# mcuboard.net
KiCad netlist of a schematic drawn in EAGLE
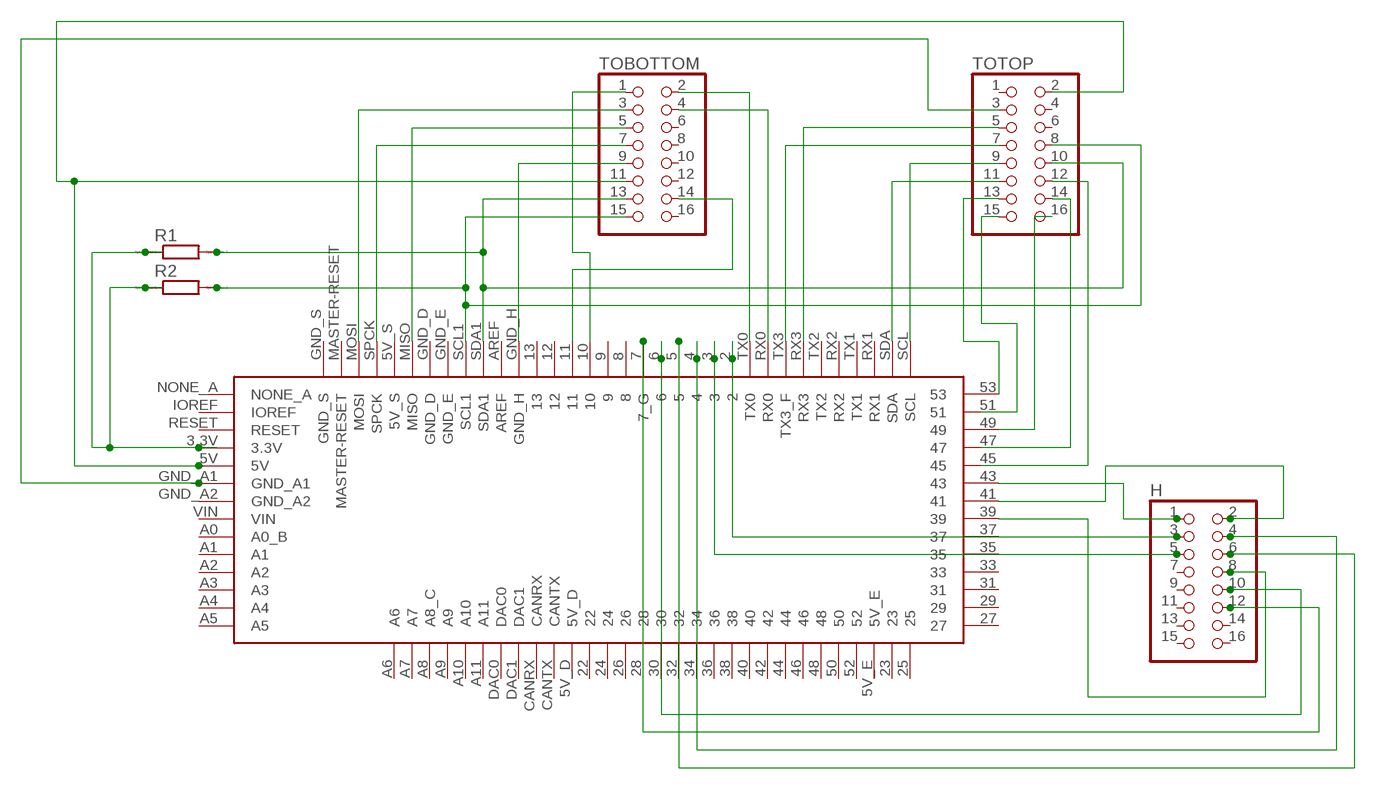
[diagram p0: schematic, sheet 1]

(export (version "E")
  (design (tool "Eeschema 10.0.6"))
  (components
    (comp (ref "H")
      (value "PINHD-2X8")
      (footprint "eagle-import:2X08")
      (libsource (lib "eagle-import") (part "PINHD-2X8"))
    )
    (comp (ref "R1")
      (value "R-EU_0207_12")
      (footprint "eagle-import:0207_12")
      (libsource (lib "eagle-import") (part "R-EU_0207_12"))
    )
    (comp (ref "R2")
      (value "R-EU_0207_12")
      (footprint "eagle-import:0207_12")
      (libsource (lib "eagle-import") (part "R-EU_0207_12"))
    )
    (comp (ref "TOBOTTOM")
      (value "PINHD-2X8")
      (footprint "eagle-import:2X08")
      (libsource (lib "eagle-import") (part "PINHD-2X8"))
    )
    (comp (ref "TOTOP")
      (value "PINHD-2X8")
      (footprint "eagle-import:2X08")
      (libsource (lib "eagle-import") (part "PINHD-2X8"))
    )
    (comp (ref "U$1")
      (value "IDUINO1")
      (footprint "eagle-import:IDUINO_PAC")
      (libsource (lib "eagle-import") (part "IDUINO1"))
    )
  )
  (nets
    (net (code "1") (name "Net-(H-Pad1)") (class "Default")
      (node (ref "H") (pin "1") (pinfunction "1_1") (pintype "passive"))
      (node (ref "U$1") (pin "43") (pinfunction "43_43") (pintype "bidirectional"))
    )
    (net (code "2") (name "Net-(H-Pad2)") (class "Default")
      (node (ref "H") (pin "2") (pinfunction "2_2") (pintype "passive"))
      (node (ref "U$1") (pin "41") (pinfunction "41_41") (pintype "bidirectional"))
    )
    (net (code "3") (name "Net-(H-Pad3)") (class "Default")
      (node (ref "H") (pin "3") (pinfunction "3_3") (pintype "passive"))
      (node (ref "U$1") (pin "2") (pinfunction "2_2") (pintype "bidirectional"))
    )
    (net (code "4") (name "Net-(H-Pad4)") (class "Default")
      (node (ref "H") (pin "4") (pinfunction "4_4") (pintype "passive"))
      (node (ref "U$1") (pin "4") (pinfunction "4_4") (pintype "bidirectional"))
    )
    (net (code "5") (name "Net-(H-Pad5)") (class "Default")
      (node (ref "H") (pin "5") (pinfunction "5_5") (pintype "passive"))
      (node (ref "U$1") (pin "3") (pinfunction "3_3") (pintype "bidirectional"))
    )
    (net (code "6") (name "Net-(H-Pad6)") (class "Default")
      (node (ref "H") (pin "6") (pinfunction "6_6") (pintype "passive"))
      (node (ref "U$1") (pin "5") (pinfunction "5_5") (pintype "bidirectional"))
    )
    (net (code "7") (name "Net-(H-Pad8)") (class "Default")
      (node (ref "H") (pin "8") (pinfunction "8_8") (pintype "passive"))
      (node (ref "U$1") (pin "39") (pinfunction "39_39") (pintype "bidirectional"))
    )
    (net (code "8") (name "Net-(H-Pad10)") (class "Default")
      (node (ref "H") (pin "10") (pinfunction "10_10") (pintype "passive"))
      (node (ref "U$1") (pin "6") (pinfunction "6_6") (pintype "bidirectional"))
    )
    (net (code "9") (name "Net-(R1-Pad1)") (class "Default")
      (node (ref "R1") (pin "1") (pinfunction "1_1") (pintype "passive"))
      (node (ref "R2") (pin "1") (pinfunction "1_1") (pintype "passive"))
      (node (ref "U$1") (pin "3.3V") (pinfunction "3.3V_3.3V") (pintype "bidirectional"))
    )
    (net (code "10") (name "Net-(R1-Pad2)") (class "Default")
      (node (ref "R1") (pin "2") (pinfunction "2_2") (pintype "passive"))
      (node (ref "TOBOTTOM") (pin "13") (pinfunction "13_13") (pintype "passive"))
      (node (ref "TOTOP") (pin "10") (pinfunction "10_10") (pintype "passive"))
      (node (ref "U$1") (pin "SDA1") (pinfunction "SDA1_SDA1") (pintype "bidirectional"))
    )
    (net (code "11") (name "Net-(R2-Pad2)") (class "Default")
      (node (ref "R2") (pin "2") (pinfunction "2_2") (pintype "passive"))
      (node (ref "TOBOTTOM") (pin "15") (pinfunction "15_15") (pintype "passive"))
      (node (ref "TOTOP") (pin "8") (pinfunction "8_8") (pintype "passive"))
      (node (ref "U$1") (pin "SCL1") (pinfunction "SCL1_SCL1") (pintype "bidirectional"))
    )
    (net (code "12") (name "Net-(TOBOTTOM-Pad1)") (class "Default")
      (node (ref "TOBOTTOM") (pin "1") (pinfunction "1_1") (pintype "passive"))
      (node (ref "U$1") (pin "10") (pinfunction "10_10") (pintype "bidirectional"))
    )
    (net (code "13") (name "Net-(TOBOTTOM-Pad2)") (class "Default")
      (node (ref "TOBOTTOM") (pin "2") (pinfunction "2_2") (pintype "passive"))
      (node (ref "U$1") (pin "TX0") (pinfunction "TX0_TX0") (pintype "bidirectional"))
    )
    (net (code "14") (name "Net-(TOBOTTOM-Pad3)") (class "Default")
      (node (ref "TOBOTTOM") (pin "3") (pinfunction "3_3") (pintype "passive"))
      (node (ref "U$1") (pin "MOSI") (pinfunction "MOSI_MOSI") (pintype "bidirectional"))
    )
    (net (code "15") (name "Net-(TOBOTTOM-Pad4)") (class "Default")
      (node (ref "TOBOTTOM") (pin "4") (pinfunction "4_4") (pintype "passive"))
      (node (ref "U$1") (pin "RX0") (pinfunction "RX0_RX0") (pintype "bidirectional"))
    )
    (net (code "16") (name "Net-(TOBOTTOM-Pad5)") (class "Default")
      (node (ref "TOBOTTOM") (pin "5") (pinfunction "5_5") (pintype "passive"))
      (node (ref "U$1") (pin "MISO") (pinfunction "MISO_MISO") (pintype "bidirectional"))
    )
    (net (code "17") (name "Net-(TOBOTTOM-Pad7)") (class "Default")
      (node (ref "TOBOTTOM") (pin "7") (pinfunction "7_7") (pintype "passive"))
      (node (ref "U$1") (pin "SPCK") (pinfunction "SPCK_SPCK") (pintype "bidirectional"))
    )
    (net (code "18") (name "Net-(TOBOTTOM-Pad9)") (class "Default")
      (node (ref "TOBOTTOM") (pin "9") (pinfunction "9_9") (pintype "passive"))
      (node (ref "U$1") (pin "GND_H") (pinfunction "GND_H_GND_H") (pintype "bidirectional"))
    )
    (net (code "19") (name "Net-(TOBOTTOM-Pad11)") (class "Default")
      (node (ref "TOBOTTOM") (pin "11") (pinfunction "11_11") (pintype "passive"))
      (node (ref "TOTOP") (pin "2") (pinfunction "2_2") (pintype "passive"))
      (node (ref "U$1") (pin "5V") (pinfunction "5V_5V") (pintype "bidirectional"))
    )
    (net (code "20") (name "Net-(TOBOTTOM-Pad14)") (class "Default")
      (node (ref "TOBOTTOM") (pin "14") (pinfunction "14_14") (pintype "passive"))
      (node (ref "U$1") (pin "11") (pinfunction "11_11") (pintype "bidirectional"))
    )
    (net (code "21") (name "Net-(TOTOP-Pad3)") (class "Default")
      (node (ref "TOTOP") (pin "3") (pinfunction "3_3") (pintype "passive"))
      (node (ref "U$1") (pin "GND_A1") (pinfunction "GND_A1_GND_A1") (pintype "bidirectional"))
    )
    (net (code "22") (name "Net-(TOTOP-Pad5)") (class "Default")
      (node (ref "TOTOP") (pin "5") (pinfunction "5_5") (pintype "passive"))
      (node (ref "U$1") (pin "RX3") (pinfunction "RX3_RX3") (pintype "bidirectional"))
    )
    (net (code "23") (name "Net-(TOTOP-Pad9)") (class "Default")
      (node (ref "TOTOP") (pin "9") (pinfunction "9_9") (pintype "passive"))
      (node (ref "U$1") (pin "SCL") (pinfunction "SCL_SCL") (pintype "bidirectional"))
    )
    (net (code "24") (name "Net-(TOTOP-Pad11)") (class "Default")
      (node (ref "TOTOP") (pin "11") (pinfunction "11_11") (pintype "passive"))
      (node (ref "U$1") (pin "SDA") (pinfunction "SDA_SDA") (pintype "bidirectional"))
    )
    (net (code "25") (name "Net-(TOTOP-Pad13)") (class "Default")
      (node (ref "TOTOP") (pin "13") (pinfunction "13_13") (pintype "passive"))
      (node (ref "U$1") (pin "53") (pinfunction "53_53") (pintype "bidirectional"))
    )
    (net (code "26") (name "Net-(TOTOP-Pad16)") (class "Default")
      (node (ref "TOTOP") (pin "16") (pinfunction "16_16") (pintype "passive"))
      (node (ref "U$1") (pin "49") (pinfunction "49_49") (pintype "bidirectional"))
    )
    (net (code "27") (name "Net-(U$1-7_G)") (class "Default")
      (node (ref "H") (pin "12") (pinfunction "12_12") (pintype "passive"))
      (node (ref "U$1") (pin "7") (pinfunction "7_G_7") (pintype "bidirectional"))
    )
    (net (code "28") (name "Net-(U$1-TX3_F)") (class "Default")
      (node (ref "TOTOP") (pin "7") (pinfunction "7_7") (pintype "passive"))
      (node (ref "U$1") (pin "TX3") (pinfunction "TX3_F_TX3") (pintype "bidirectional"))
    )
    (net (code "29") (name "unconnected-(H-Pad7)") (class "Default")
      (node (ref "H") (pin "7") (pinfunction "7_7") (pintype "passive"))
    )
    (net (code "30") (name "unconnected-(H-Pad9)") (class "Default")
      (node (ref "H") (pin "9") (pinfunction "9_9") (pintype "passive"))
    )
    (net (code "31") (name "unconnected-(H-Pad11)") (class "Default")
      (node (ref "H") (pin "11") (pinfunction "11_11") (pintype "passive"))
    )
    (net (code "32") (name "unconnected-(H-Pad13)") (class "Default")
      (node (ref "H") (pin "13") (pinfunction "13_13") (pintype "passive"))
    )
    (net (code "33") (name "unconnected-(H-Pad14)") (class "Default")
      (node (ref "H") (pin "14") (pinfunction "14_14") (pintype "passive"))
    )
    (net (code "34") (name "unconnected-(H-Pad15)") (class "Default")
      (node (ref "H") (pin "15") (pinfunction "15_15") (pintype "passive"))
    )
    (net (code "35") (name "unconnected-(H-Pad16)") (class "Default")
      (node (ref "H") (pin "16") (pinfunction "16_16") (pintype "passive"))
    )
    (net (code "36") (name "unconnected-(TOBOTTOM-Pad6)") (class "Default")
      (node (ref "TOBOTTOM") (pin "6") (pinfunction "6_6") (pintype "passive"))
    )
    (net (code "37") (name "unconnected-(TOBOTTOM-Pad8)") (class "Default")
      (node (ref "TOBOTTOM") (pin "8") (pinfunction "8_8") (pintype "passive"))
    )
    (net (code "38") (name "unconnected-(TOBOTTOM-Pad10)") (class "Default")
      (node (ref "TOBOTTOM") (pin "10") (pinfunction "10_10") (pintype "passive"))
    )
    (net (code "39") (name "unconnected-(TOBOTTOM-Pad12)") (class "Default")
      (node (ref "TOBOTTOM") (pin "12") (pinfunction "12_12") (pintype "passive"))
    )
    (net (code "40") (name "unconnected-(TOBOTTOM-Pad16)") (class "Default")
      (node (ref "TOBOTTOM") (pin "16") (pinfunction "16_16") (pintype "passive"))
    )
    (net (code "41") (name "unconnected-(TOTOP-Pad1)") (class "Default")
      (node (ref "TOTOP") (pin "1") (pinfunction "1_1") (pintype "passive"))
    )
    (net (code "42") (name "unconnected-(TOTOP-Pad4)") (class "Default")
      (node (ref "TOTOP") (pin "4") (pinfunction "4_4") (pintype "passive"))
    )
    (net (code "43") (name "unconnected-(TOTOP-Pad6)") (class "Default")
      (node (ref "TOTOP") (pin "6") (pinfunction "6_6") (pintype "passive"))
    )
    (net (code "44") (name "unconnected-(TOTOP-Pad12)") (class "Default")
      (node (ref "TOTOP") (pin "12") (pinfunction "12_12") (pintype "passive"))
    )
    (net (code "45") (name "unconnected-(TOTOP-Pad14)") (class "Default")
      (node (ref "TOTOP") (pin "14") (pinfunction "14_14") (pintype "passive"))
    )
    (net (code "46") (name "unconnected-(TOTOP-Pad15)") (class "Default")
      (node (ref "TOTOP") (pin "15") (pinfunction "15_15") (pintype "passive"))
    )
    (net (code "47") (name "unconnected-(U$1-A0_B-PadA0)") (class "Default")
      (node (ref "U$1") (pin "A0") (pinfunction "A0_B_A0") (pintype "bidirectional"))
    )
    (net (code "48") (name "unconnected-(U$1-A8_C-PadA8)") (class "Default")
      (node (ref "U$1") (pin "A8") (pinfunction "A8_C_A8") (pintype "bidirectional"))
    )
    (net (code "49") (name "unconnected-(U$1-Pad5V_D)") (class "Default")
      (node (ref "U$1") (pin "5V_D") (pinfunction "5V_D_5V_D") (pintype "bidirectional"))
    )
    (net (code "50") (name "unconnected-(U$1-Pad5V_E)") (class "Default")
      (node (ref "U$1") (pin "5V_E") (pinfunction "5V_E_5V_E") (pintype "bidirectional"))
    )
    (net (code "51") (name "unconnected-(U$1-Pad5V_S)") (class "Default")
      (node (ref "U$1") (pin "5V_S") (pinfunction "5V_S_5V_S") (pintype "bidirectional"))
    )
    (net (code "52") (name "unconnected-(U$1-Pad8)") (class "Default")
      (node (ref "U$1") (pin "8") (pinfunction "8_8") (pintype "bidirectional"))
    )
    (net (code "53") (name "unconnected-(U$1-Pad9)") (class "Default")
      (node (ref "U$1") (pin "9") (pinfunction "9_9") (pintype "bidirectional"))
    )
    (net (code "54") (name "unconnected-(U$1-Pad12)") (class "Default")
      (node (ref "U$1") (pin "12") (pinfunction "12_12") (pintype "bidirectional"))
    )
    (net (code "55") (name "unconnected-(U$1-Pad13)") (class "Default")
      (node (ref "U$1") (pin "13") (pinfunction "13_13") (pintype "bidirectional"))
    )
    (net (code "56") (name "unconnected-(U$1-Pad22)") (class "Default")
      (node (ref "U$1") (pin "22") (pinfunction "22_22") (pintype "bidirectional"))
    )
    (net (code "57") (name "unconnected-(U$1-Pad23)") (class "Default")
      (node (ref "U$1") (pin "23") (pinfunction "23_23") (pintype "bidirectional"))
    )
    (net (code "58") (name "unconnected-(U$1-Pad24)") (class "Default")
      (node (ref "U$1") (pin "24") (pinfunction "24_24") (pintype "bidirectional"))
    )
    (net (code "59") (name "unconnected-(U$1-Pad25)") (class "Default")
      (node (ref "U$1") (pin "25") (pinfunction "25_25") (pintype "bidirectional"))
    )
    (net (code "60") (name "unconnected-(U$1-Pad26)") (class "Default")
      (node (ref "U$1") (pin "26") (pinfunction "26_26") (pintype "bidirectional"))
    )
    (net (code "61") (name "unconnected-(U$1-Pad27)") (class "Default")
      (node (ref "U$1") (pin "27") (pinfunction "27_27") (pintype "bidirectional"))
    )
    (net (code "62") (name "unconnected-(U$1-Pad28)") (class "Default")
      (node (ref "U$1") (pin "28") (pinfunction "28_28") (pintype "bidirectional"))
    )
    (net (code "63") (name "unconnected-(U$1-Pad29)") (class "Default")
      (node (ref "U$1") (pin "29") (pinfunction "29_29") (pintype "bidirectional"))
    )
    (net (code "64") (name "unconnected-(U$1-Pad30)") (class "Default")
      (node (ref "U$1") (pin "30") (pinfunction "30_30") (pintype "bidirectional"))
    )
    (net (code "65") (name "unconnected-(U$1-Pad31)") (class "Default")
      (node (ref "U$1") (pin "31") (pinfunction "31_31") (pintype "bidirectional"))
    )
    (net (code "66") (name "unconnected-(U$1-Pad32)") (class "Default")
      (node (ref "U$1") (pin "32") (pinfunction "32_32") (pintype "bidirectional"))
    )
    (net (code "67") (name "unconnected-(U$1-Pad33)") (class "Default")
      (node (ref "U$1") (pin "33") (pinfunction "33_33") (pintype "bidirectional"))
    )
    (net (code "68") (name "unconnected-(U$1-Pad34)") (class "Default")
      (node (ref "U$1") (pin "34") (pinfunction "34_34") (pintype "bidirectional"))
    )
    (net (code "69") (name "unconnected-(U$1-Pad35)") (class "Default")
      (node (ref "U$1") (pin "35") (pinfunction "35_35") (pintype "bidirectional"))
    )
    (net (code "70") (name "unconnected-(U$1-Pad36)") (class "Default")
      (node (ref "U$1") (pin "36") (pinfunction "36_36") (pintype "bidirectional"))
    )
    (net (code "71") (name "unconnected-(U$1-Pad37)") (class "Default")
      (node (ref "U$1") (pin "37") (pinfunction "37_37") (pintype "bidirectional"))
    )
    (net (code "72") (name "unconnected-(U$1-Pad38)") (class "Default")
      (node (ref "U$1") (pin "38") (pinfunction "38_38") (pintype "bidirectional"))
    )
    (net (code "73") (name "unconnected-(U$1-Pad40)") (class "Default")
      (node (ref "U$1") (pin "40") (pinfunction "40_40") (pintype "bidirectional"))
    )
    (net (code "74") (name "unconnected-(U$1-Pad42)") (class "Default")
      (node (ref "U$1") (pin "42") (pinfunction "42_42") (pintype "bidirectional"))
    )
    (net (code "75") (name "unconnected-(U$1-Pad44)") (class "Default")
      (node (ref "U$1") (pin "44") (pinfunction "44_44") (pintype "bidirectional"))
    )
    (net (code "76") (name "unconnected-(U$1-Pad45)") (class "Default")
      (node (ref "U$1") (pin "45") (pinfunction "45_45") (pintype "bidirectional"))
    )
    (net (code "77") (name "unconnected-(U$1-Pad46)") (class "Default")
      (node (ref "U$1") (pin "46") (pinfunction "46_46") (pintype "bidirectional"))
    )
    (net (code "78") (name "unconnected-(U$1-Pad47)") (class "Default")
      (node (ref "U$1") (pin "47") (pinfunction "47_47") (pintype "bidirectional"))
    )
    (net (code "79") (name "unconnected-(U$1-Pad48)") (class "Default")
      (node (ref "U$1") (pin "48") (pinfunction "48_48") (pintype "bidirectional"))
    )
    (net (code "80") (name "unconnected-(U$1-Pad50)") (class "Default")
      (node (ref "U$1") (pin "50") (pinfunction "50_50") (pintype "bidirectional"))
    )
    (net (code "81") (name "unconnected-(U$1-Pad51)") (class "Default")
      (node (ref "U$1") (pin "51") (pinfunction "51_51") (pintype "bidirectional"))
    )
    (net (code "82") (name "unconnected-(U$1-Pad52)") (class "Default")
      (node (ref "U$1") (pin "52") (pinfunction "52_52") (pintype "bidirectional"))
    )
    (net (code "83") (name "unconnected-(U$1-PadA1)") (class "Default")
      (node (ref "U$1") (pin "A1") (pinfunction "A1_A1") (pintype "bidirectional"))
    )
    (net (code "84") (name "unconnected-(U$1-PadA2)") (class "Default")
      (node (ref "U$1") (pin "A2") (pinfunction "A2_A2") (pintype "bidirectional"))
    )
    (net (code "85") (name "unconnected-(U$1-PadA3)") (class "Default")
      (node (ref "U$1") (pin "A3") (pinfunction "A3_A3") (pintype "bidirectional"))
    )
    (net (code "86") (name "unconnected-(U$1-PadA4)") (class "Default")
      (node (ref "U$1") (pin "A4") (pinfunction "A4_A4") (pintype "bidirectional"))
    )
    (net (code "87") (name "unconnected-(U$1-PadA5)") (class "Default")
      (node (ref "U$1") (pin "A5") (pinfunction "A5_A5") (pintype "bidirectional"))
    )
    (net (code "88") (name "unconnected-(U$1-PadA6)") (class "Default")
      (node (ref "U$1") (pin "A6") (pinfunction "A6_A6") (pintype "bidirectional"))
    )
    (net (code "89") (name "unconnected-(U$1-PadA7)") (class "Default")
      (node (ref "U$1") (pin "A7") (pinfunction "A7_A7") (pintype "bidirectional"))
    )
    (net (code "90") (name "unconnected-(U$1-PadA9)") (class "Default")
      (node (ref "U$1") (pin "A9") (pinfunction "A9_A9") (pintype "bidirectional"))
    )
    (net (code "91") (name "unconnected-(U$1-PadA10)") (class "Default")
      (node (ref "U$1") (pin "A10") (pinfunction "A10_A10") (pintype "bidirectional"))
    )
    (net (code "92") (name "unconnected-(U$1-PadA11)") (class "Default")
      (node (ref "U$1") (pin "A11") (pinfunction "A11_A11") (pintype "bidirectional"))
    )
    (net (code "93") (name "unconnected-(U$1-PadAREF)") (class "Default")
      (node (ref "U$1") (pin "AREF") (pinfunction "AREF_AREF") (pintype "bidirectional"))
    )
    (net (code "94") (name "unconnected-(U$1-PadCANRX)") (class "Default")
      (node (ref "U$1") (pin "CANRX") (pinfunction "CANRX_CANRX") (pintype "bidirectional"))
    )
    (net (code "95") (name "unconnected-(U$1-PadCANTX)") (class "Default")
      (node (ref "U$1") (pin "CANTX") (pinfunction "CANTX_CANTX") (pintype "bidirectional"))
    )
    (net (code "96") (name "unconnected-(U$1-PadDAC0)") (class "Default")
      (node (ref "U$1") (pin "DAC0") (pinfunction "DAC0_DAC0") (pintype "bidirectional"))
    )
    (net (code "97") (name "unconnected-(U$1-PadDAC1)") (class "Default")
      (node (ref "U$1") (pin "DAC1") (pinfunction "DAC1_DAC1") (pintype "bidirectional"))
    )
    (net (code "98") (name "unconnected-(U$1-PadGND_A2)") (class "Default")
      (node (ref "U$1") (pin "GND_A2") (pinfunction "GND_A2_GND_A2") (pintype "bidirectional"))
    )
    (net (code "99") (name "unconnected-(U$1-PadGND_D)") (class "Default")
      (node (ref "U$1") (pin "GND_D") (pinfunction "GND_D_GND_D") (pintype "bidirectional"))
    )
    (net (code "100") (name "unconnected-(U$1-PadGND_E)") (class "Default")
      (node (ref "U$1") (pin "GND_E") (pinfunction "GND_E_GND_E") (pintype "bidirectional"))
    )
    (net (code "101") (name "unconnected-(U$1-PadGND_S)") (class "Default")
      (node (ref "U$1") (pin "GND_S") (pinfunction "GND_S_GND_S") (pintype "bidirectional"))
    )
    (net (code "102") (name "unconnected-(U$1-PadIOREF)") (class "Default")
      (node (ref "U$1") (pin "IOREF") (pinfunction "IOREF_IOREF") (pintype "bidirectional"))
    )
    (net (code "103") (name "unconnected-(U$1-PadMASTER-RESET)") (class "Default")
      (node (ref "U$1") (pin "MASTER-RESET") (pinfunction "MASTER-RESET_MASTER-RESET") (pintype "bidirectional"))
    )
    (net (code "104") (name "unconnected-(U$1-PadNONE_A)") (class "Default")
      (node (ref "U$1") (pin "NONE_A") (pinfunction "NONE_A_NONE_A") (pintype "bidirectional"))
    )
    (net (code "105") (name "unconnected-(U$1-PadRESET)") (class "Default")
      (node (ref "U$1") (pin "RESET") (pinfunction "RESET_RESET") (pintype "bidirectional"))
    )
    (net (code "106") (name "unconnected-(U$1-PadRX1)") (class "Default")
      (node (ref "U$1") (pin "RX1") (pinfunction "RX1_RX1") (pintype "bidirectional"))
    )
    (net (code "107") (name "unconnected-(U$1-PadRX2)") (class "Default")
      (node (ref "U$1") (pin "RX2") (pinfunction "RX2_RX2") (pintype "bidirectional"))
    )
    (net (code "108") (name "unconnected-(U$1-PadTX1)") (class "Default")
      (node (ref "U$1") (pin "TX1") (pinfunction "TX1_TX1") (pintype "bidirectional"))
    )
    (net (code "109") (name "unconnected-(U$1-PadTX2)") (class "Default")
      (node (ref "U$1") (pin "TX2") (pinfunction "TX2_TX2") (pintype "bidirectional"))
    )
    (net (code "110") (name "unconnected-(U$1-PadVIN)") (class "Default")
      (node (ref "U$1") (pin "VIN") (pinfunction "VIN_VIN") (pintype "bidirectional"))
    )
  )
)
